# FOC-PMSM.net
KiCad netlist of a schematic drawn in Altium Designer
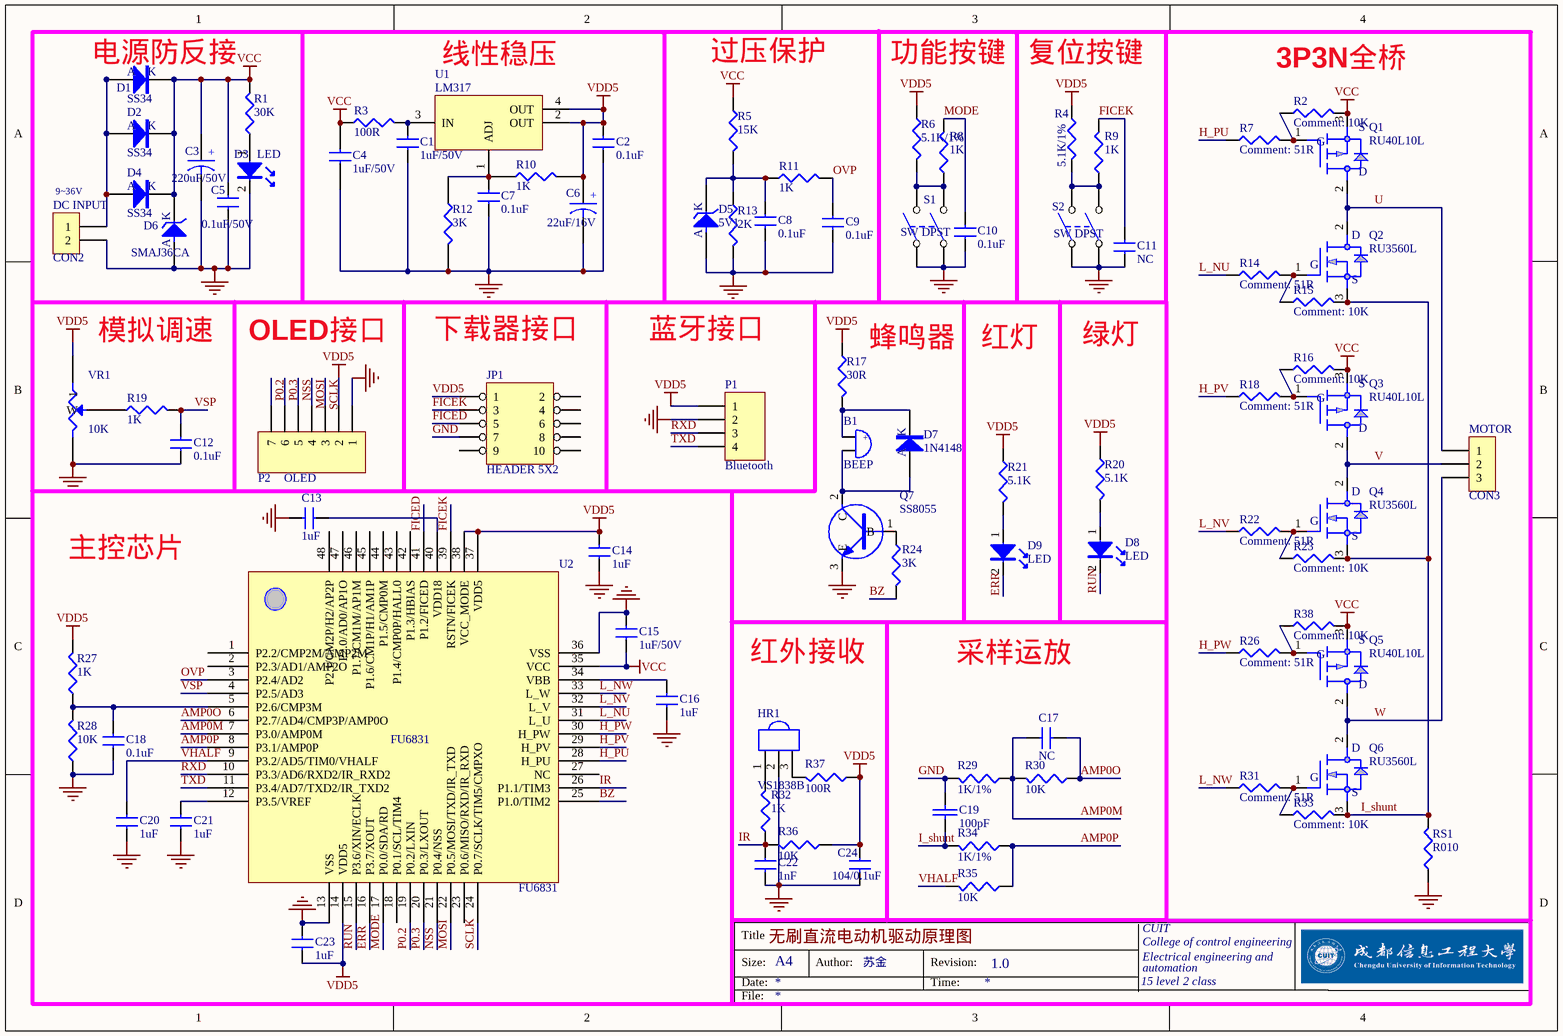
[diagram p0: FOC-PMSM.SchDoc]

(export (version "E")
  (design (tool "Eeschema 10.0.6"))
  (components
    (comp (ref "B1")
      (value "BEEP")
      (footprint "BEEP 7.6x12x9.5")
      (description "蜂鸣器")
      (libsource (lib "蜂鸣器") (part "BEEP"))
    )
    (comp (ref "C1")
      (value "1uF/50V")
      (footprint "C0805")
      (description "Capacitor")
      (libsource (lib "") (part "CAP_1"))
    )
    (comp (ref "C2")
      (value "0.1uF")
      (footprint "C0805")
      (description "Capacitor")
      (libsource (lib "") (part "CAP_1"))
    )
    (comp (ref "C3")
      (value "220uF/50V")
      (footprint "CE5-10/16")
      (description "Capacitor")
      (libsource (lib "*") (part "CAP极性"))
    )
    (comp (ref "C4")
      (value "1uF/50V")
      (footprint "C0805")
      (description "Capacitor")
      (libsource (lib "*") (part "CAP"))
    )
    (comp (ref "C5")
      (value "0.1uF/50V")
      (footprint "C0805")
      (description "Capacitor")
      (libsource (lib "") (part "CAP_1"))
    )
    (comp (ref "C6")
      (value "22uF/16V")
      (footprint "DIP-EC2.0X5X11")
      (description "Capacitor")
      (libsource (lib "*") (part "CAP极性"))
    )
    (comp (ref "C7")
      (value "0.1uF")
      (footprint "C0805")
      (description "Capacitor")
      (libsource (lib "") (part "CAP_1"))
    )
    (comp (ref "C8")
      (value "0.1uF")
      (footprint "C0805")
      (description "Capacitor")
      (libsource (lib "") (part "CAP_1"))
    )
    (comp (ref "C9")
      (value "0.1uF")
      (footprint "C0805")
      (description "Capacitor")
      (libsource (lib "") (part "CAP_1"))
    )
    (comp (ref "C10")
      (value "0.1uF")
      (footprint "C0805")
      (description "Capacitor")
      (libsource (lib "") (part "CAP_1"))
    )
    (comp (ref "C11")
      (value "NC")
      (footprint "C0805")
      (description "Capacitor")
      (libsource (lib "") (part "CAP_1"))
    )
    (comp (ref "C12")
      (value "0.1uF")
      (footprint "C0805")
      (description "Capacitor")
      (libsource (lib "") (part "CAP_1"))
    )
    (comp (ref "C13")
      (value "1uF")
      (footprint "C0805")
      (description "Capacitor")
      (libsource (lib "") (part "CAP_1"))
    )
    (comp (ref "C14")
      (value "1uF")
      (footprint "C0805")
      (description "Capacitor")
      (libsource (lib "") (part "CAP_1"))
    )
    (comp (ref "C15")
      (value "1uF/50V")
      (footprint "C0805")
      (description "Capacitor")
      (libsource (lib "") (part "CAP_1"))
    )
    (comp (ref "C16")
      (value "1uF")
      (footprint "C0805")
      (description "Capacitor")
      (libsource (lib "") (part "CAP_1"))
    )
    (comp (ref "C17")
      (value "NC")
      (footprint "C0805")
      (description "Capacitor")
      (libsource (lib "") (part "CAP_1"))
    )
    (comp (ref "C18")
      (value "0.1uF")
      (footprint "C0805")
      (description "Capacitor")
      (libsource (lib "") (part "CAP_1"))
    )
    (comp (ref "C19")
      (value "100pF")
      (footprint "C0805")
      (description "Capacitor")
      (libsource (lib "") (part "CAP_2"))
    )
    (comp (ref "C20")
      (value "1uF")
      (footprint "C0805")
      (description "Capacitor")
      (libsource (lib "") (part "CAP_1"))
    )
    (comp (ref "C21")
      (value "1uF")
      (footprint "C0805")
      (description "Capacitor")
      (libsource (lib "") (part "CAP_1"))
    )
    (comp (ref "C22")
      (value "1nF")
      (footprint "C0805")
      (description "Capacitor")
      (libsource (lib "") (part "CAP_1"))
    )
    (comp (ref "C23")
      (value "1uF")
      (footprint "C0805")
      (description "Capacitor")
      (libsource (lib "") (part "CAP_1"))
    )
    (comp (ref "C24")
      (value "104/0.1uF")
      (footprint "C0805")
      (description "Capacitor")
      (libsource (lib "") (part "CAP_1"))
    )
    (comp (ref "D1")
      (value "SS34")
      (footprint "SMB")
      (description "Diode")
      (libsource (lib "*") (part "DIODE"))
    )
    (comp (ref "D2")
      (value "SS34")
      (footprint "SMB")
      (description "Diode")
      (libsource (lib "*") (part "DIODE"))
    )
    (comp (ref "D3") (value "LED") (footprint "LED0805") (libsource (lib "*") (part "LED")))
    (comp (ref "D4")
      (value "SS34")
      (footprint "SMB")
      (description "Diode")
      (libsource (lib "*") (part "DIODE"))
    )
    (comp (ref "D5")
      (value "5V1")
      (footprint "SOD-123")
      (description "Zener Diode")
      (libsource (lib "*") (part "ZENER3"))
    )
    (comp (ref "D6")
      (value "SMAJ36CA")
      (footprint "SMA")
      (description "Zener Diode")
      (libsource (lib "*") (part "ZENER3"))
    )
    (comp (ref "D7")
      (value "1N4148")
      (footprint "SOD-123")
      (description "Diode")
      (libsource (lib "") (part "DIODE_1"))
    )
    (comp (ref "D8") (value "LED") (footprint "LED0805") (libsource (lib "*") (part "LED")))
    (comp (ref "D9") (value "LED") (footprint "LED0805") (libsource (lib "*") (part "LED")))
    (comp (ref "DC INPUT")
      (value "CON2")
      (footprint "250-2P")
      (description "Connector")
      (libsource (lib "*") (part "CON2"))
    )
    (comp (ref "HR1")
      (value "VS1838B")
      (footprint "VS1838B-B_H")
      (description "红外接收头")
      (libsource (lib "传感器") (part "VS1838B"))
    )
    (comp (ref "JP1")
      (value "HEADER 5X2")
      (footprint "DC3-14P 2*7  2.54")
      (libsource (lib "*") (part "HEADER 5X2"))
    )
    (comp (ref "MOTOR")
      (value "CON3")
      (footprint "250-3P")
      (description "Connector")
      (libsource (lib "*") (part "CON3"))
    )
    (comp (ref "P1")
      (value "Bluetooth")
      (footprint "HDR1X4")
      (description "Header, 4-Pin")
      (fields (field (name "PUBLISHER") "Altium Limited"))
      (libsource (lib "智能车51开发板V2.0") (part "Header 4"))
    )
    (comp (ref "P2")
      (value "OLED")
      (footprint "HDR1X7")
      (description "Header, 7-Pin")
      (fields (field (name "PUBLISHER") "Altium Limited"))
      (libsource (lib "Miscellaneous Connectors") (part "Header 7"))
    )
    (comp (ref "Q1") (value "RU40L10L") (footprint "TO-252-3L") (libsource (lib "*") (part "CAP_4")))
    (comp (ref "Q2") (value "RU3560L") (footprint "TO-252-3L") (libsource (lib "*") (part "CAP_2")))
    (comp (ref "Q3") (value "RU40L10L") (footprint "TO-252-3L") (libsource (lib "*") (part "CAP_4")))
    (comp (ref "Q4") (value "RU3560L") (footprint "TO-252-3L") (libsource (lib "*") (part "CAP_2")))
    (comp (ref "Q5") (value "RU40L10L") (footprint "TO-252-3L") (libsource (lib "*") (part "CAP_4")))
    (comp (ref "Q6") (value "RU3560L") (footprint "TO-252-3L") (libsource (lib "*") (part "CAP_2")))
    (comp (ref "Q7")
      (value "SS8055")
      (footprint "SOT-23")
      (description "NPN Transistor")
      (libsource (lib "*") (part "NPN"))
    )
    (comp (ref "R1")
      (value "30K")
      (footprint "R0805")
      (description "RES")
      (libsource (lib "*") (part "RES-SMD"))
    )
    (comp (ref "R2")
      (value "10K")
      (footprint "R0805")
      (description "RES")
      (libsource (lib "*") (part "RES-SMD"))
    )
    (comp (ref "R3")
      (value "100R")
      (footprint "R2512")
      (description "RES")
      (libsource (lib "*") (part "RES-SMD"))
    )
    (comp (ref "R4") (value "5.1K/1%") (footprint "R0805") (libsource (lib "*") (part "RES(SMD)")))
    (comp (ref "R5")
      (value "15K")
      (footprint "R0805")
      (description "RES")
      (libsource (lib "*") (part "RES-SMD"))
    )
    (comp (ref "R6") (value "5.1K/1%") (footprint "R0805") (libsource (lib "*") (part "RES(SMD)")))
    (comp (ref "R7")
      (value "51R")
      (footprint "R0805")
      (description "RES")
      (libsource (lib "*") (part "RES-SMD"))
    )
    (comp (ref "R8") (value "1K") (footprint "R0805") (libsource (lib "*") (part "RES(SMD)")))
    (comp (ref "R9") (value "1K") (footprint "R0805") (libsource (lib "*") (part "RES(SMD)")))
    (comp (ref "R10")
      (value "1K")
      (footprint "R0805")
      (description "RES")
      (libsource (lib "") (part "RES-SMD_1"))
    )
    (comp (ref "R11")
      (value "1K")
      (footprint "R0805")
      (description "RES")
      (libsource (lib "*") (part "RES-SMD"))
    )
    (comp (ref "R12")
      (value "3K")
      (footprint "R0805")
      (description "RES")
      (libsource (lib "") (part "RES-SMD_1"))
    )
    (comp (ref "R13")
      (value "2K")
      (footprint "R0805")
      (description "RES")
      (libsource (lib "*") (part "RES-SMD"))
    )
    (comp (ref "R14")
      (value "51R")
      (footprint "R0805")
      (description "RES")
      (libsource (lib "*") (part "RES-SMD"))
    )
    (comp (ref "R15")
      (value "10K")
      (footprint "R0805")
      (description "RES")
      (libsource (lib "*") (part "RES-SMD"))
    )
    (comp (ref "R16")
      (value "10K")
      (footprint "R0805")
      (description "RES")
      (libsource (lib "*") (part "RES-SMD"))
    )
    (comp (ref "R17")
      (value "30R")
      (footprint "R0805")
      (description "RES")
      (libsource (lib "*") (part "RES-SMD"))
    )
    (comp (ref "R18")
      (value "51R")
      (footprint "R0805")
      (description "RES")
      (libsource (lib "*") (part "RES-SMD"))
    )
    (comp (ref "R19") (value "1K") (footprint "R0805") (libsource (lib "*") (part "RES(SMD)")))
    (comp (ref "R20")
      (value "5.1K")
      (footprint "R0805")
      (description "RES")
      (libsource (lib "*") (part "RES-SMD"))
    )
    (comp (ref "R21")
      (value "5.1K")
      (footprint "R0805")
      (description "RES")
      (libsource (lib "*") (part "RES-SMD"))
    )
    (comp (ref "R22")
      (value "51R")
      (footprint "R0805")
      (description "RES")
      (libsource (lib "*") (part "RES-SMD"))
    )
    (comp (ref "R23")
      (value "10K")
      (footprint "R0805")
      (description "RES")
      (libsource (lib "*") (part "RES-SMD"))
    )
    (comp (ref "R24")
      (value "3K")
      (footprint "R0805")
      (description "RES")
      (libsource (lib "*") (part "RES-SMD"))
    )
    (comp (ref "R26")
      (value "51R")
      (footprint "R0805")
      (description "RES")
      (libsource (lib "*") (part "RES-SMD"))
    )
    (comp (ref "R27")
      (value "1K")
      (footprint "R0805")
      (description "RES")
      (libsource (lib "*") (part "RES-SMD"))
    )
    (comp (ref "R28")
      (value "10K")
      (footprint "R0805")
      (description "RES")
      (libsource (lib "*") (part "RES-SMD"))
    )
    (comp (ref "R29") (value "1K/1%") (footprint "R0805") (libsource (lib "*") (part "RES(SMD)")))
    (comp (ref "R30") (value "10K") (footprint "R0805") (libsource (lib "*") (part "RES(SMD)")))
    (comp (ref "R31")
      (value "51R")
      (footprint "R0805")
      (description "RES")
      (libsource (lib "*") (part "RES-SMD"))
    )
    (comp (ref "R32")
      (value "1K")
      (footprint "R0805")
      (description "RES")
      (libsource (lib "*") (part "RES-SMD"))
    )
    (comp (ref "R33")
      (value "10K")
      (footprint "R0805")
      (description "RES")
      (libsource (lib "*") (part "RES-SMD"))
    )
    (comp (ref "R34") (value "1K/1%") (footprint "R0805") (libsource (lib "*") (part "RES(SMD)")))
    (comp (ref "R35") (value "10K") (footprint "R0805") (libsource (lib "*") (part "RES(SMD)")))
    (comp (ref "R36")
      (value "10K")
      (footprint "R0805")
      (description "RES")
      (libsource (lib "*") (part "RES-SMD"))
    )
    (comp (ref "R37")
      (value "100R")
      (footprint "R0805")
      (description "RES")
      (libsource (lib "*") (part "RES-SMD"))
    )
    (comp (ref "R38")
      (value "10K")
      (footprint "R0805")
      (description "RES")
      (libsource (lib "*") (part "RES-SMD"))
    )
    (comp (ref "RS1")
      (value "R010")
      (footprint "R2512")
      (description "RES")
      (libsource (lib "*") (part "RES-SMD"))
    )
    (comp (ref "S1") (value "SW DPST") (footprint "SW-6/6") (libsource (lib "*") (part "SW DPST")))
    (comp (ref "S2") (value "SW DPST") (footprint "SW-6/6") (libsource (lib "*") (part "SW DPST")))
    (comp (ref "U1") (value "LM317") (footprint "SOT-223") (libsource (lib "*") (part "LM317")))
    (comp (ref "U2") (value "FU6831") (footprint "LQFP48") (libsource (lib "*") (part "FU6831")))
    (comp (ref "VR1")
      (value "10K")
      (footprint "VR6")
      (description "Potentiometer")
      (libsource (lib "*") (part "RV-3296"))
    )
  )
  (nets
    (net (code "1") (name "/AMP0M") (class "Default")
      (node (ref "C17") (pin "1") (pinfunction "1_1") (pintype "passive"))
      (node (ref "R29") (pin "1") (pinfunction "1_1") (pintype "passive"))
      (node (ref "R30") (pin "2") (pinfunction "2_2") (pintype "passive"))
      (node (ref "U2") (pin "7") (pinfunction "P3.0/AMP0M_7") (pintype "passive"))
    )
    (net (code "2") (name "/AMP0O") (class "Default")
      (node (ref "C17") (pin "2") (pinfunction "2_2") (pintype "passive"))
      (node (ref "R30") (pin "1") (pinfunction "1_1") (pintype "passive"))
      (node (ref "U2") (pin "6") (pinfunction "P2.7/AD4/CMP3P/AMP0O_6") (pintype "passive"))
    )
    (net (code "3") (name "/AMP0P") (class "Default")
      (node (ref "R34") (pin "1") (pinfunction "1_1") (pintype "passive"))
      (node (ref "R35") (pin "1") (pinfunction "1_1") (pintype "passive"))
      (node (ref "U2") (pin "8") (pinfunction "P3.1/AMP0P_8") (pintype "passive"))
    )
    (net (code "4") (name "/BZ") (class "Default")
      (node (ref "R24") (pin "2") (pinfunction "2_2") (pintype "passive"))
      (node (ref "U2") (pin "25") (pinfunction "P1.0/TIM2_25") (pintype "passive"))
    )
    (net (code "5") (name "/ERR") (class "Default")
      (node (ref "D9") (pin "2") (pinfunction "2_2") (pintype "passive"))
      (node (ref "U2") (pin "16") (pinfunction "P3.7/XOUT_16") (pintype "passive"))
    )
    (net (code "6") (name "/FICED") (class "Default")
      (node (ref "JP1") (pin "5") (pinfunction "5_5") (pintype "passive"))
      (node (ref "U2") (pin "41") (pinfunction "P1.2/FICED_41") (pintype "passive"))
    )
    (net (code "7") (name "/FICEK") (class "Default")
      (node (ref "C11") (pin "1") (pinfunction "1_1") (pintype "passive"))
      (node (ref "JP1") (pin "3") (pinfunction "3_3") (pintype "passive"))
      (node (ref "R9") (pin "2") (pinfunction "2_2") (pintype "passive"))
      (node (ref "U2") (pin "39") (pinfunction "RSTN/FICEK_39") (pintype "passive"))
    )
    (net (code "8") (name "/H_PU") (class "Default")
      (node (ref "R7") (pin "1") (pinfunction "1_1") (pintype "passive"))
      (node (ref "U2") (pin "28") (pinfunction "H_PU_28") (pintype "passive"))
    )
    (net (code "9") (name "/H_PV") (class "Default")
      (node (ref "R18") (pin "1") (pinfunction "1_1") (pintype "passive"))
      (node (ref "U2") (pin "29") (pinfunction "H_PV_29") (pintype "passive"))
    )
    (net (code "10") (name "/H_PW") (class "Default")
      (node (ref "R26") (pin "1") (pinfunction "1_1") (pintype "passive"))
      (node (ref "U2") (pin "30") (pinfunction "H_PW_30") (pintype "passive"))
    )
    (net (code "11") (name "/IR") (class "Default")
      (node (ref "C22") (pin "1") (pinfunction "1_1") (pintype "passive"))
      (node (ref "R32") (pin "1") (pinfunction "1_1") (pintype "passive"))
      (node (ref "R36") (pin "2") (pinfunction "2_2") (pintype "passive"))
      (node (ref "U2") (pin "26") (pinfunction "P1.1/TIM3_26") (pintype "passive"))
    )
    (net (code "12") (name "/I_shunt") (class "Default")
      (node (ref "C19") (pin "2") (pinfunction "2_2") (pintype "passive"))
      (node (ref "Q2") (pin "3") (pinfunction "S_3") (pintype "passive"))
      (node (ref "Q4") (pin "3") (pinfunction "S_3") (pintype "passive"))
      (node (ref "Q6") (pin "3") (pinfunction "S_3") (pintype "passive"))
      (node (ref "R15") (pin "2") (pinfunction "2_2") (pintype "passive"))
      (node (ref "R23") (pin "2") (pinfunction "2_2") (pintype "passive"))
      (node (ref "R33") (pin "2") (pinfunction "2_2") (pintype "passive"))
      (node (ref "R34") (pin "2") (pinfunction "2_2") (pintype "passive"))
      (node (ref "RS1") (pin "2") (pinfunction "2_2") (pintype "passive"))
    )
    (net (code "13") (name "/L_NU") (class "Default")
      (node (ref "R14") (pin "1") (pinfunction "1_1") (pintype "passive"))
      (node (ref "U2") (pin "31") (pinfunction "L_U_31") (pintype "passive"))
    )
    (net (code "14") (name "/L_NV") (class "Default")
      (node (ref "R22") (pin "1") (pinfunction "1_1") (pintype "passive"))
      (node (ref "U2") (pin "32") (pinfunction "L_V_32") (pintype "passive"))
    )
    (net (code "15") (name "/L_NW") (class "Default")
      (node (ref "R31") (pin "1") (pinfunction "1_1") (pintype "passive"))
      (node (ref "U2") (pin "33") (pinfunction "L_W_33") (pintype "passive"))
    )
    (net (code "16") (name "/MODE") (class "Default")
      (node (ref "C10") (pin "1") (pinfunction "1_1") (pintype "passive"))
      (node (ref "R8") (pin "2") (pinfunction "2_2") (pintype "passive"))
      (node (ref "U2") (pin "17") (pinfunction "P0.0/SDA/RD_17") (pintype "passive"))
    )
    (net (code "17") (name "/MOSI") (class "Default")
      (node (ref "P2") (pin "4") (pinfunction "4_4") (pintype "passive"))
      (node (ref "U2") (pin "22") (pinfunction "P0.5/MOSI/TXD/IR_TXD_22") (pintype "passive"))
    )
    (net (code "18") (name "/NSS") (class "Default")
      (node (ref "P2") (pin "5") (pinfunction "5_5") (pintype "passive"))
      (node (ref "U2") (pin "21") (pinfunction "P0.4/NSS_21") (pintype "passive"))
    )
    (net (code "19") (name "/OVP") (class "Default")
      (node (ref "C9") (pin "1") (pinfunction "1_1") (pintype "passive"))
      (node (ref "R11") (pin "2") (pinfunction "2_2") (pintype "passive"))
      (node (ref "U2") (pin "3") (pinfunction "P2.4/AD2_3") (pintype "passive"))
    )
    (net (code "20") (name "/P0.2") (class "Default")
      (node (ref "P2") (pin "7") (pinfunction "7_7") (pintype "passive"))
      (node (ref "U2") (pin "19") (pinfunction "P0.2/LXIN_19") (pintype "passive"))
    )
    (net (code "21") (name "/P0.3") (class "Default")
      (node (ref "P2") (pin "6") (pinfunction "6_6") (pintype "passive"))
      (node (ref "U2") (pin "20") (pinfunction "P0.3/LXOUT_20") (pintype "passive"))
    )
    (net (code "22") (name "/RUN") (class "Default")
      (node (ref "D8") (pin "2") (pinfunction "2_2") (pintype "passive"))
      (node (ref "U2") (pin "15") (pinfunction "P3.6/XIN/ECLK_15") (pintype "passive"))
    )
    (net (code "23") (name "/RXD") (class "Default")
      (node (ref "P1") (pin "3") (pinfunction "3_3") (pintype "passive"))
      (node (ref "U2") (pin "10") (pinfunction "P3.3/AD6/RXD2/IR_RXD2_10") (pintype "passive"))
    )
    (net (code "24") (name "/SCLK") (class "Default")
      (node (ref "P2") (pin "3") (pinfunction "3_3") (pintype "passive"))
      (node (ref "U2") (pin "24") (pinfunction "P0.7/SCLK/TIM5/CMPXO_24") (pintype "passive"))
    )
    (net (code "25") (name "/TXD") (class "Default")
      (node (ref "P1") (pin "4") (pinfunction "4_4") (pintype "passive"))
      (node (ref "U2") (pin "11") (pinfunction "P3.4/AD7/TXD2/IR_TXD2_11") (pintype "passive"))
    )
    (net (code "26") (name "/U") (class "Default")
      (node (ref "MOTOR") (pin "1") (pinfunction "1_1") (pintype "passive"))
      (node (ref "Q1") (pin "2") (pinfunction "D_2") (pintype "passive"))
      (node (ref "Q2") (pin "2") (pinfunction "D_2") (pintype "passive"))
    )
    (net (code "27") (name "/V") (class "Default")
      (node (ref "MOTOR") (pin "2") (pinfunction "2_2") (pintype "passive"))
      (node (ref "Q3") (pin "2") (pinfunction "D_2") (pintype "passive"))
      (node (ref "Q4") (pin "2") (pinfunction "D_2") (pintype "passive"))
    )
    (net (code "28") (name "/VHALF") (class "Default")
      (node (ref "C20") (pin "2") (pinfunction "2_2") (pintype "passive"))
      (node (ref "R35") (pin "2") (pinfunction "2_2") (pintype "passive"))
      (node (ref "U2") (pin "9") (pinfunction "P3.2/AD5/TIM0/VHALF_9") (pintype "passive"))
    )
    (net (code "29") (name "/VSP") (class "Default")
      (node (ref "C12") (pin "1") (pinfunction "1_1") (pintype "passive"))
      (node (ref "R19") (pin "2") (pinfunction "2_2") (pintype "passive"))
      (node (ref "U2") (pin "4") (pinfunction "P2.5/AD3_4") (pintype "passive"))
    )
    (net (code "30") (name "/W") (class "Default")
      (node (ref "MOTOR") (pin "3") (pinfunction "3_3") (pintype "passive"))
      (node (ref "Q5") (pin "2") (pinfunction "D_2") (pintype "passive"))
      (node (ref "Q6") (pin "2") (pinfunction "D_2") (pintype "passive"))
    )
    (net (code "31") (name "GND") (class "Default")
      (node (ref "C1") (pin "2") (pinfunction "2_2") (pintype "passive"))
      (node (ref "C10") (pin "2") (pinfunction "2_2") (pintype "passive"))
      (node (ref "C11") (pin "2") (pinfunction "2_2") (pintype "passive"))
      (node (ref "C12") (pin "2") (pinfunction "2_2") (pintype "passive"))
      (node (ref "C13") (pin "1") (pinfunction "1_1") (pintype "passive"))
      (node (ref "C14") (pin "2") (pinfunction "2_2") (pintype "passive"))
      (node (ref "C15") (pin "1") (pinfunction "1_1") (pintype "passive"))
      (node (ref "C16") (pin "2") (pinfunction "2_2") (pintype "passive"))
      (node (ref "C18") (pin "1") (pinfunction "1_1") (pintype "passive"))
      (node (ref "C19") (pin "1") (pinfunction "1_1") (pintype "passive"))
      (node (ref "C2") (pin "2") (pinfunction "2_2") (pintype "passive"))
      (node (ref "C20") (pin "1") (pinfunction "1_1") (pintype "passive"))
      (node (ref "C21") (pin "1") (pinfunction "1_1") (pintype "passive"))
      (node (ref "C22") (pin "2") (pinfunction "2_2") (pintype "passive"))
      (node (ref "C23") (pin "1") (pinfunction "1_1") (pintype "passive"))
      (node (ref "C24") (pin "2") (pinfunction "2_2") (pintype "passive"))
      (node (ref "C3") (pin "2") (pinfunction "2_2") (pintype "passive"))
      (node (ref "C4") (pin "2") (pinfunction "2_2") (pintype "passive"))
      (node (ref "C5") (pin "2") (pinfunction "2_2") (pintype "passive"))
      (node (ref "C6") (pin "2") (pinfunction "2_2") (pintype "passive"))
      (node (ref "C7") (pin "2") (pinfunction "2_2") (pintype "passive"))
      (node (ref "C8") (pin "2") (pinfunction "2_2") (pintype "passive"))
      (node (ref "C9") (pin "2") (pinfunction "2_2") (pintype "passive"))
      (node (ref "D3") (pin "2") (pinfunction "2_2") (pintype "passive"))
      (node (ref "D5") (pin "1") (pinfunction "A_1") (pintype "passive"))
      (node (ref "D6") (pin "1") (pinfunction "A_1") (pintype "passive"))
      (node (ref "DC INPUT") (pin "2") (pinfunction "2_2") (pintype "passive"))
      (node (ref "HR1") (pin "2") (pinfunction "K_2") (pintype "passive"))
      (node (ref "JP1") (pin "7") (pinfunction "7_7") (pintype "passive"))
      (node (ref "P1") (pin "2") (pinfunction "2_2") (pintype "passive"))
      (node (ref "P2") (pin "1") (pinfunction "1_1") (pintype "passive"))
      (node (ref "Q7") (pin "3") (pinfunction "E_3") (pintype "passive"))
      (node (ref "R12") (pin "2") (pinfunction "2_2") (pintype "passive"))
      (node (ref "R13") (pin "2") (pinfunction "2_2") (pintype "passive"))
      (node (ref "R28") (pin "1") (pinfunction "1_1") (pintype "passive"))
      (node (ref "R29") (pin "2") (pinfunction "2_2") (pintype "passive"))
      (node (ref "RS1") (pin "1") (pinfunction "1_1") (pintype "passive"))
      (node (ref "S1") (pin "1") (pinfunction "COMMON1_1") (pintype "passive"))
      (node (ref "S2") (pin "1") (pinfunction "COMMON1_1") (pintype "passive"))
      (node (ref "U2") (pin "13") (pinfunction "VSS_13") (pintype "passive"))
      (node (ref "U2") (pin "36") (pinfunction "VSS_36") (pintype "passive"))
      (node (ref "VR1") (pin "3") (pinfunction "3_3") (pintype "passive"))
    )
    (net (code "32") (name "Net-(D1-Pad1)") (class "Default")
      (node (ref "D1") (pin "1") (pintype "passive"))
      (node (ref "D2") (pin "1") (pintype "passive"))
      (node (ref "D4") (pin "1") (pintype "passive"))
      (node (ref "DC INPUT") (pin "1") (pinfunction "1_1") (pintype "passive"))
    )
    (net (code "33") (name "Net-(D3-Pad1)") (class "Default")
      (node (ref "D3") (pin "1") (pinfunction "1_1") (pintype "passive"))
      (node (ref "R1") (pin "1") (pinfunction "1_1") (pintype "passive"))
    )
    (net (code "34") (name "Net-(D5-K)") (class "Default")
      (node (ref "C8") (pin "1") (pinfunction "1_1") (pintype "passive"))
      (node (ref "D5") (pin "2") (pinfunction "K_2") (pintype "passive"))
      (node (ref "R11") (pin "1") (pinfunction "1_1") (pintype "passive"))
      (node (ref "R13") (pin "1") (pinfunction "1_1") (pintype "passive"))
      (node (ref "R5") (pin "2") (pinfunction "2_2") (pintype "passive"))
    )
    (net (code "35") (name "Net-(D7-K)") (class "Default")
      (node (ref "B1") (pin "1") (pinfunction "1_1") (pintype "passive"))
      (node (ref "D7") (pin "2") (pinfunction "K_2") (pintype "passive"))
      (node (ref "R17") (pin "2") (pinfunction "2_2") (pintype "passive"))
    )
    (net (code "36") (name "Net-(D8-Pad1)") (class "Default")
      (node (ref "D8") (pin "1") (pinfunction "1_1") (pintype "passive"))
      (node (ref "R20") (pin "2") (pinfunction "2_2") (pintype "passive"))
    )
    (net (code "37") (name "Net-(D9-Pad1)") (class "Default")
      (node (ref "D9") (pin "1") (pinfunction "1_1") (pintype "passive"))
      (node (ref "R21") (pin "2") (pinfunction "2_2") (pintype "passive"))
    )
    (net (code "38") (name "Net-(HR1-A)") (class "Default")
      (node (ref "HR1") (pin "1") (pinfunction "A_1") (pintype "passive"))
      (node (ref "R32") (pin "2") (pinfunction "2_2") (pintype "passive"))
    )
    (net (code "39") (name "Net-(HR1-E)") (class "Default")
      (node (ref "HR1") (pin "3") (pinfunction "E_3") (pintype "passive"))
      (node (ref "R37") (pin "2") (pinfunction "2_2") (pintype "passive"))
    )
    (net (code "40") (name "Net-(Q1-G)") (class "Default")
      (node (ref "Q1") (pin "1") (pinfunction "G_1") (pintype "passive"))
      (node (ref "R2") (pin "1") (pinfunction "1_1") (pintype "passive"))
      (node (ref "R7") (pin "2") (pinfunction "2_2") (pintype "passive"))
    )
    (net (code "41") (name "Net-(Q2-G)") (class "Default")
      (node (ref "Q2") (pin "1") (pinfunction "G_1") (pintype "passive"))
      (node (ref "R14") (pin "2") (pinfunction "2_2") (pintype "passive"))
      (node (ref "R15") (pin "1") (pinfunction "1_1") (pintype "passive"))
    )
    (net (code "42") (name "Net-(Q3-G)") (class "Default")
      (node (ref "Q3") (pin "1") (pinfunction "G_1") (pintype "passive"))
      (node (ref "R16") (pin "1") (pinfunction "1_1") (pintype "passive"))
      (node (ref "R18") (pin "2") (pinfunction "2_2") (pintype "passive"))
    )
    (net (code "43") (name "Net-(Q4-G)") (class "Default")
      (node (ref "Q4") (pin "1") (pinfunction "G_1") (pintype "passive"))
      (node (ref "R22") (pin "2") (pinfunction "2_2") (pintype "passive"))
      (node (ref "R23") (pin "1") (pinfunction "1_1") (pintype "passive"))
    )
    (net (code "44") (name "Net-(Q5-G)") (class "Default")
      (node (ref "Q5") (pin "1") (pinfunction "G_1") (pintype "passive"))
      (node (ref "R26") (pin "2") (pinfunction "2_2") (pintype "passive"))
      (node (ref "R38") (pin "1") (pinfunction "1_1") (pintype "passive"))
    )
    (net (code "45") (name "Net-(Q6-G)") (class "Default")
      (node (ref "Q6") (pin "1") (pinfunction "G_1") (pintype "passive"))
      (node (ref "R31") (pin "2") (pinfunction "2_2") (pintype "passive"))
      (node (ref "R33") (pin "1") (pinfunction "1_1") (pintype "passive"))
    )
    (net (code "46") (name "Net-(Q7-B)") (class "Default")
      (node (ref "Q7") (pin "1") (pinfunction "B_1") (pintype "passive"))
      (node (ref "R24") (pin "1") (pinfunction "1_1") (pintype "passive"))
    )
    (net (code "47") (name "Net-(Q7-C)") (class "Default")
      (node (ref "B1") (pin "2") (pinfunction "2_2") (pintype "passive"))
      (node (ref "D7") (pin "1") (pintype "passive"))
      (node (ref "Q7") (pin "2") (pinfunction "C_2") (pintype "passive"))
    )
    (net (code "48") (name "Net-(R19-Pad1)") (class "Default")
      (node (ref "R19") (pin "1") (pinfunction "1_1") (pintype "passive"))
      (node (ref "VR1") (pin "W") (pinfunction "W_W") (pintype "passive"))
    )
    (net (code "49") (name "Net-(S1-NO1)") (class "Default")
      (node (ref "R6") (pin "2") (pinfunction "2_2") (pintype "passive"))
      (node (ref "R8") (pin "1") (pinfunction "1_1") (pintype "passive"))
      (node (ref "S1") (pin "2") (pinfunction "NO1_2") (pintype "passive"))
    )
    (net (code "50") (name "Net-(S2-NO1)") (class "Default")
      (node (ref "R4") (pin "2") (pinfunction "2_2") (pintype "passive"))
      (node (ref "R9") (pin "1") (pinfunction "1_1") (pintype "passive"))
      (node (ref "S2") (pin "2") (pinfunction "NO1_2") (pintype "passive"))
    )
    (net (code "51") (name "Net-(U1-ADJ)") (class "Default")
      (node (ref "C7") (pin "1") (pinfunction "1_1") (pintype "passive"))
      (node (ref "R10") (pin "1") (pinfunction "1_1") (pintype "passive"))
      (node (ref "R12") (pin "1") (pinfunction "1_1") (pintype "passive"))
      (node (ref "U1") (pin "1") (pinfunction "ADJ_1") (pintype "passive"))
    )
    (net (code "52") (name "Net-(U1-IN)") (class "Default")
      (node (ref "C1") (pin "1") (pinfunction "1_1") (pintype "passive"))
      (node (ref "R3") (pin "2") (pinfunction "2_2") (pintype "passive"))
      (node (ref "U1") (pin "3") (pinfunction "IN_3") (pintype "passive"))
    )
    (net (code "53") (name "Net-(U2-P2.6{slash}CMP3M)") (class "Default")
      (node (ref "C18") (pin "2") (pinfunction "2_2") (pintype "passive"))
      (node (ref "R27") (pin "1") (pinfunction "1_1") (pintype "passive"))
      (node (ref "R28") (pin "2") (pinfunction "2_2") (pintype "passive"))
      (node (ref "U2") (pin "5") (pinfunction "P2.6/CMP3M_5") (pintype "passive"))
    )
    (net (code "54") (name "Net-(U2-P3.5{slash}VREF)") (class "Default")
      (node (ref "C21") (pin "2") (pinfunction "2_2") (pintype "passive"))
      (node (ref "U2") (pin "12") (pinfunction "P3.5/VREF_12") (pintype "passive"))
    )
    (net (code "55") (name "Net-(U2-VBB)") (class "Default")
      (node (ref "C16") (pin "1") (pinfunction "1_1") (pintype "passive"))
      (node (ref "U2") (pin "34") (pinfunction "VBB_34") (pintype "passive"))
    )
    (net (code "56") (name "Net-(U2-VDD18)") (class "Default")
      (node (ref "C13") (pin "2") (pinfunction "2_2") (pintype "passive"))
      (node (ref "U2") (pin "40") (pinfunction "VDD18_40") (pintype "passive"))
    )
    (net (code "57") (name "VCC") (class "Default")
      (node (ref "C15") (pin "2") (pinfunction "2_2") (pintype "passive"))
      (node (ref "C3") (pin "1") (pinfunction "1_1") (pintype "passive"))
      (node (ref "C4") (pin "1") (pinfunction "1_1") (pintype "passive"))
      (node (ref "C5") (pin "1") (pinfunction "1_1") (pintype "passive"))
      (node (ref "D1") (pin "2") (pinfunction "K_2") (pintype "passive"))
      (node (ref "D2") (pin "2") (pinfunction "K_2") (pintype "passive"))
      (node (ref "D4") (pin "2") (pinfunction "K_2") (pintype "passive"))
      (node (ref "D6") (pin "2") (pinfunction "K_2") (pintype "passive"))
      (node (ref "Q1") (pin "3") (pinfunction "S_3") (pintype "passive"))
      (node (ref "Q3") (pin "3") (pinfunction "S_3") (pintype "passive"))
      (node (ref "Q5") (pin "3") (pinfunction "S_3") (pintype "passive"))
      (node (ref "R1") (pin "2") (pinfunction "2_2") (pintype "passive"))
      (node (ref "R16") (pin "2") (pinfunction "2_2") (pintype "passive"))
      (node (ref "R2") (pin "2") (pinfunction "2_2") (pintype "passive"))
      (node (ref "R3") (pin "1") (pinfunction "1_1") (pintype "passive"))
      (node (ref "R38") (pin "2") (pinfunction "2_2") (pintype "passive"))
      (node (ref "R5") (pin "1") (pinfunction "1_1") (pintype "passive"))
      (node (ref "U2") (pin "35") (pinfunction "VCC_35") (pintype "passive"))
    )
    (net (code "58") (name "VDD5") (class "Default")
      (node (ref "C14") (pin "1") (pinfunction "1_1") (pintype "passive"))
      (node (ref "C2") (pin "1") (pinfunction "1_1") (pintype "passive"))
      (node (ref "C23") (pin "2") (pinfunction "2_2") (pintype "passive"))
      (node (ref "C24") (pin "1") (pinfunction "1_1") (pintype "passive"))
      (node (ref "C6") (pin "1") (pinfunction "1_1") (pintype "passive"))
      (node (ref "JP1") (pin "1") (pinfunction "1_1") (pintype "passive"))
      (node (ref "P1") (pin "1") (pinfunction "1_1") (pintype "passive"))
      (node (ref "P2") (pin "2") (pinfunction "2_2") (pintype "passive"))
      (node (ref "R10") (pin "2") (pinfunction "2_2") (pintype "passive"))
      (node (ref "R17") (pin "1") (pinfunction "1_1") (pintype "passive"))
      (node (ref "R20") (pin "1") (pinfunction "1_1") (pintype "passive"))
      (node (ref "R21") (pin "1") (pinfunction "1_1") (pintype "passive"))
      (node (ref "R27") (pin "2") (pinfunction "2_2") (pintype "passive"))
      (node (ref "R36") (pin "1") (pinfunction "1_1") (pintype "passive"))
      (node (ref "R37") (pin "1") (pinfunction "1_1") (pintype "passive"))
      (node (ref "R4") (pin "1") (pinfunction "1_1") (pintype "passive"))
      (node (ref "R6") (pin "1") (pinfunction "1_1") (pintype "passive"))
      (node (ref "U1") (pin "2") (pinfunction "OUT_2") (pintype "passive"))
      (node (ref "U1") (pin "4") (pinfunction "OUT_4") (pintype "passive"))
      (node (ref "U2") (pin "14") (pinfunction "VDD5_14") (pintype "passive"))
      (node (ref "U2") (pin "37") (pinfunction "VDD5_37") (pintype "passive"))
      (node (ref "U2") (pin "38") (pinfunction "VCC_MODE_38") (pintype "passive"))
      (node (ref "VR1") (pin "1") (pinfunction "1_1") (pintype "passive"))
    )
    (net (code "59") (name "unconnected-(JP1-Pad2)") (class "Default")
      (node (ref "JP1") (pin "2") (pinfunction "2_2") (pintype "passive"))
    )
    (net (code "60") (name "unconnected-(JP1-Pad4)") (class "Default")
      (node (ref "JP1") (pin "4") (pinfunction "4_4") (pintype "passive"))
    )
    (net (code "61") (name "unconnected-(JP1-Pad6)") (class "Default")
      (node (ref "JP1") (pin "6") (pinfunction "6_6") (pintype "passive"))
    )
    (net (code "62") (name "unconnected-(JP1-Pad8)") (class "Default")
      (node (ref "JP1") (pin "8") (pinfunction "8_8") (pintype "passive"))
    )
    (net (code "63") (name "unconnected-(JP1-Pad9)") (class "Default")
      (node (ref "JP1") (pin "9") (pinfunction "9_9") (pintype "passive"))
    )
    (net (code "64") (name "unconnected-(JP1-Pad10)") (class "Default")
      (node (ref "JP1") (pin "10") (pinfunction "10_10") (pintype "passive"))
    )
    (net (code "65") (name "unconnected-(U2-NC-Pad27)") (class "Default")
      (node (ref "U2") (pin "27") (pinfunction "NC_27") (pintype "passive"))
    )
    (net (code "66") (name "unconnected-(U2-P0.1{slash}SCL{slash}TIM4-Pad18)") (class "Default")
      (node (ref "U2") (pin "18") (pinfunction "P0.1/SCL/TIM4_18") (pintype "passive"))
    )
    (net (code "67") (name "unconnected-(U2-P0.6{slash}MISO{slash}RXD{slash}IR_RXD-Pad23)") (class "Default")
      (node (ref "U2") (pin "23") (pinfunction "P0.6/MISO/RXD/IR_RXD_23") (pintype "passive"))
    )
    (net (code "68") (name "unconnected-(U2-P1.3{slash}HBIAS-Pad42)") (class "Default")
      (node (ref "U2") (pin "42") (pinfunction "P1.3/HBIAS_42") (pintype "passive"))
    )
    (net (code "69") (name "unconnected-(U2-P1.4{slash}CMP0P{slash}HALL0-Pad43)") (class "Default")
      (node (ref "U2") (pin "43") (pinfunction "P1.4/CMP0P/HALL0_43") (pintype "passive"))
    )
    (net (code "70") (name "unconnected-(U2-P1.5{slash}CMP0M-Pad44)") (class "Default")
      (node (ref "U2") (pin "44") (pinfunction "P1.5/CMP0M_44") (pintype "passive"))
    )
    (net (code "71") (name "unconnected-(U2-P1.6{slash}CM1P{slash}H1{slash}AM1P-Pad45)") (class "Default")
      (node (ref "U2") (pin "45") (pinfunction "P1.6/CM1P/H1/AM1P_45") (pintype "passive"))
    )
    (net (code "72") (name "unconnected-(U2-P1.7{slash}CM1M{slash}AP1M-Pad46)") (class "Default")
      (node (ref "U2") (pin "46") (pinfunction "P1.7/CM1M/AP1M_46") (pintype "passive"))
    )
    (net (code "73") (name "unconnected-(U2-P2.0{slash}AD0{slash}AP1O-Pad47)") (class "Default")
      (node (ref "U2") (pin "47") (pinfunction "P2.0/AD0/AP1O_47") (pintype "passive"))
    )
    (net (code "74") (name "unconnected-(U2-P2.1{slash}CM2P{slash}H2{slash}AP2P-Pad48)") (class "Default")
      (node (ref "U2") (pin "48") (pinfunction "P2.1/CM2P/H2/AP2P_48") (pintype "passive"))
    )
    (net (code "75") (name "unconnected-(U2-P2.2{slash}CMP2M{slash}AMP2M-Pad1)") (class "Default")
      (node (ref "U2") (pin "1") (pinfunction "P2.2/CMP2M/AMP2M_1") (pintype "passive"))
    )
    (net (code "76") (name "unconnected-(U2-P2.3{slash}AD1{slash}AMP2O-Pad2)") (class "Default")
      (node (ref "U2") (pin "2") (pinfunction "P2.3/AD1/AMP2O_2") (pintype "passive"))
    )
  )
)
